# Phaser.net
KiCad netlist of a schematic drawn in Altium Designer
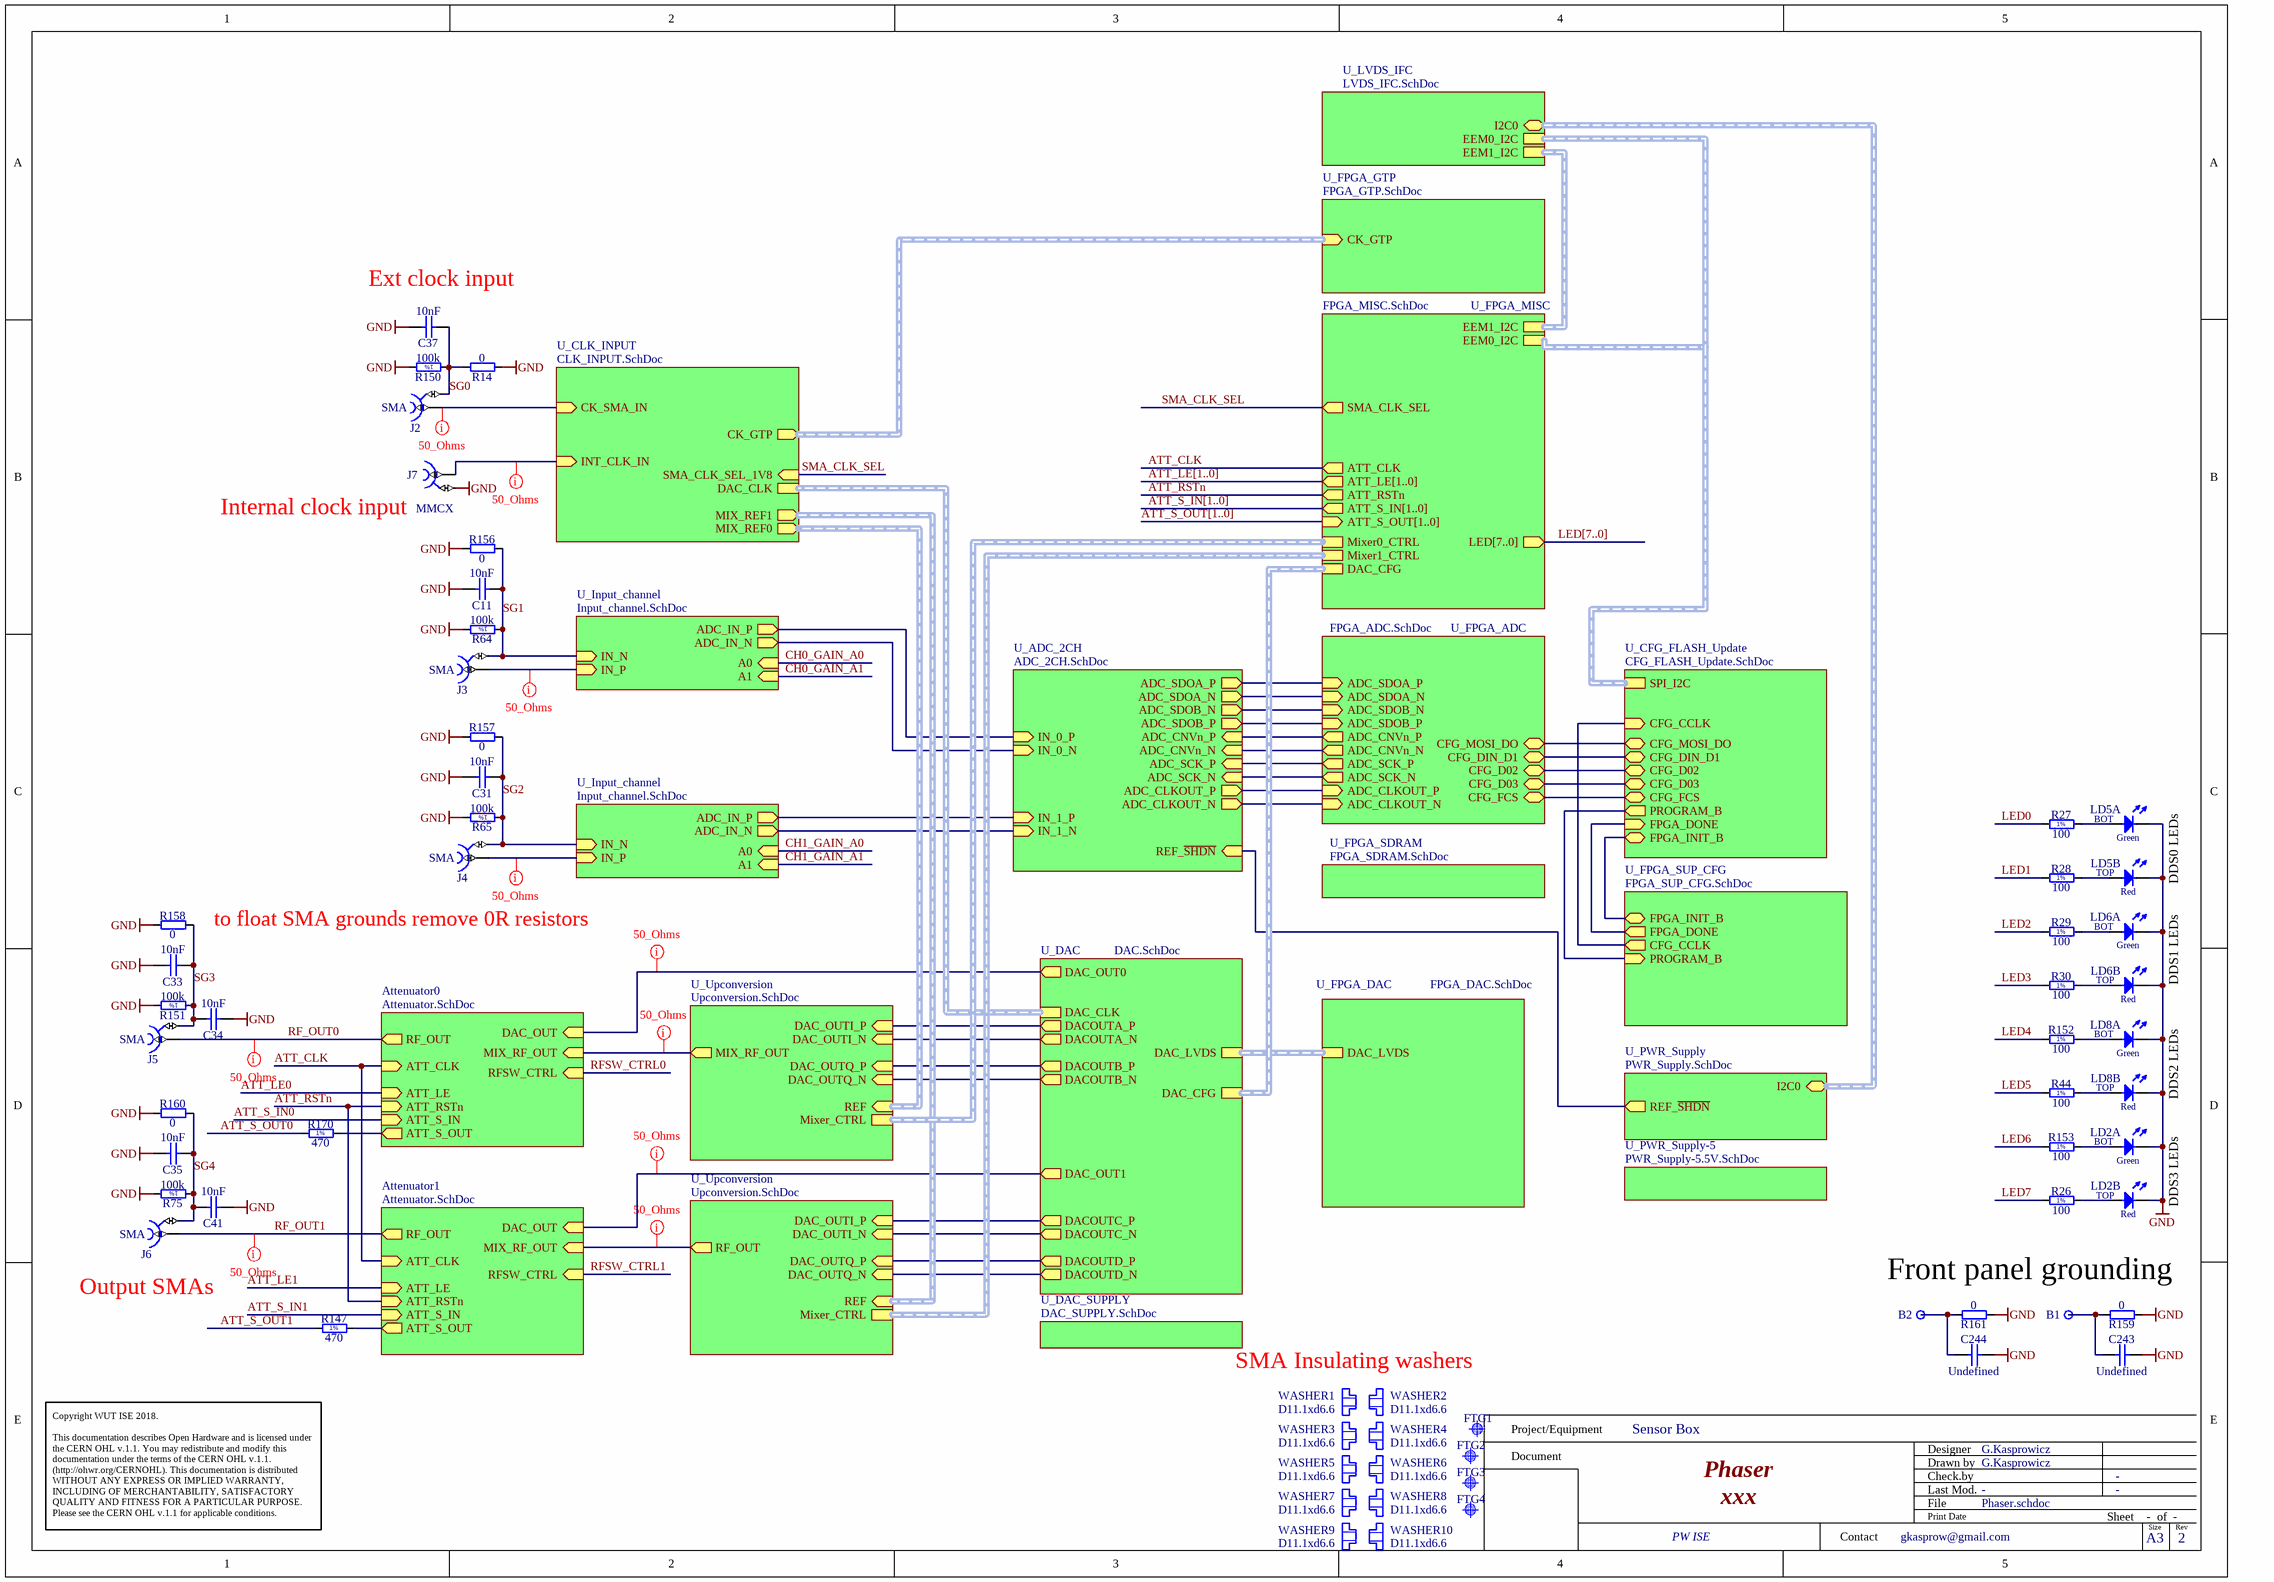
[diagram p0: Phaser.schdoc]

(export (version "E")
  (design (tool "Eeschema 10.0.6"))
  (components
    (comp (ref "B1")
      (value "Plated Hole")
      (footprint "MTG270_500")
      (description "Single Terminal Socket")
      (fields (field (name "PART NUMBER") "PLATED_HOLE2.7_PAD5.0") (field (name "AUTHOR") "CERN DEM JMW"))
      (libsource (lib "Eletro-mechanical") (part "Single Terminal Socket"))
    )
    (comp (ref "B2")
      (value "Plated Hole")
      (footprint "MTG270_500")
      (description "Single Terminal Socket")
      (fields (field (name "PART NUMBER") "PLATED_HOLE2.7_PAD5.0") (field (name "AUTHOR") "CERN DEM JMW"))
      (libsource (lib "Eletro-mechanical") (part "Single Terminal Socket"))
    )
    (comp (ref "C11")
      (value "10nF")
      (footprint "CAPC1005X55N")
      (description "Non-polarised capacitor")
      (fields
        (field (name "PART NUMBER") "CC0402_10NF_16V_10%_X7R")
        (field (name "VOLTAGE") "16V")
        (field (name "AUTHOR") "CERN DEM JLC")
      )
      (libsource (lib "Capacitors") (part "Capacitor - non polarized"))
    )
    (comp (ref "C31")
      (value "10nF")
      (footprint "CAPC1005X55N")
      (description "Non-polarised capacitor")
      (fields
        (field (name "PART NUMBER") "CC0402_10NF_16V_10%_X7R")
        (field (name "VOLTAGE") "16V")
        (field (name "AUTHOR") "CERN DEM JLC")
      )
      (libsource (lib "Capacitors") (part "Capacitor - non polarized"))
    )
    (comp (ref "C33")
      (value "10nF")
      (footprint "CAPC1005X55N")
      (description "Non-polarised capacitor")
      (fields
        (field (name "PART NUMBER") "CC0402_10NF_16V_10%_X7R")
        (field (name "VOLTAGE") "16V")
        (field (name "AUTHOR") "CERN DEM JLC")
      )
      (libsource (lib "Capacitors") (part "Capacitor - non polarized"))
    )
    (comp (ref "C34")
      (value "10nF")
      (footprint "CAPC1005X55N")
      (description "Non-polarised capacitor")
      (fields
        (field (name "PART NUMBER") "CC0402_10NF_16V_10%_X7R")
        (field (name "VOLTAGE") "16V")
        (field (name "AUTHOR") "CERN DEM JLC")
      )
      (libsource (lib "Capacitors") (part "Capacitor - non polarized"))
    )
    (comp (ref "C35")
      (value "10nF")
      (footprint "CAPC1005X55N")
      (description "Non-polarised capacitor")
      (fields
        (field (name "PART NUMBER") "CC0402_10NF_16V_10%_X7R")
        (field (name "VOLTAGE") "16V")
        (field (name "AUTHOR") "CERN DEM JLC")
      )
      (libsource (lib "Capacitors") (part "Capacitor - non polarized"))
    )
    (comp (ref "C37")
      (value "10nF")
      (footprint "CAPC1005X55N")
      (description "Non-polarised capacitor")
      (fields
        (field (name "PART NUMBER") "CC0402_10NF_16V_10%_X7R")
        (field (name "VOLTAGE") "16V")
        (field (name "AUTHOR") "CERN DEM JLC")
      )
      (libsource (lib "Capacitors") (part "Capacitor - non polarized"))
    )
    (comp (ref "C41")
      (value "10nF")
      (footprint "CAPC1005X55N")
      (description "Non-polarised capacitor")
      (fields
        (field (name "PART NUMBER") "CC0402_10NF_16V_10%_X7R")
        (field (name "VOLTAGE") "16V")
        (field (name "AUTHOR") "CERN DEM JLC")
      )
      (libsource (lib "Capacitors") (part "Capacitor - non polarized"))
    )
    (comp (ref "C243")
      (value "Undefined")
      (footprint "CAPC2012X135N")
      (description "Non-polarised capacitor")
      (fields (field (name "PART NUMBER") "CC0805_NO-VALUE") (field (name "AUTHOR") "CERN DEM JLC"))
      (libsource (lib "Capacitors") (part "Capacitor - non polarized"))
    )
    (comp (ref "C244")
      (value "Undefined")
      (footprint "CAPC2012X135N")
      (description "Non-polarised capacitor")
      (fields (field (name "PART NUMBER") "CC0805_NO-VALUE") (field (name "AUTHOR") "CERN DEM JLC"))
      (libsource (lib "Capacitors") (part "Capacitor - non polarized"))
    )
    (comp (ref "FTG1")
      (value "Use only in PCB")
      (footprint "FIDUCIAL_TOP_C100-200")
      (description "Fiducial Target")
      (fields (field (name "PART NUMBER") "FIDUCIAL_TARGET_C100-200") (field (name "AUTHOR") "CERN DEM JLC"))
      (libsource (lib "Eletro-mechanical") (part "Fiducial Target"))
    )
    (comp (ref "FTG2")
      (value "Use only in PCB")
      (footprint "FIDUCIAL_TOP_S100-200")
      (description "Fiducial Target")
      (fields (field (name "PART NUMBER") "FIDUCIAL_TARGET_S100-200") (field (name "AUTHOR") "CERN DEM JLC"))
      (libsource (lib "Eletro-mechanical") (part "Fiducial Target"))
    )
    (comp (ref "FTG3")
      (value "Use only in PCB")
      (footprint "FIDUCIAL_TOP_S200-400")
      (description "Fiducial Target")
      (fields (field (name "PART NUMBER") "FIDUCIAL_TARGET_S200-400") (field (name "AUTHOR") "CERN DEM JLC"))
      (libsource (lib "Eletro-mechanical") (part "Fiducial Target"))
    )
    (comp (ref "FTG4")
      (value "Use only in PCB")
      (footprint "FIDUCIAL_TOP_S100-200")
      (description "Fiducial Target")
      (fields (field (name "PART NUMBER") "FIDUCIAL_TARGET_S100-200") (field (name "AUTHOR") "CERN DEM JLC"))
      (libsource (lib "Eletro-mechanical") (part "Fiducial Target"))
    )
    (comp (ref "J2")
      (value "SMA")
      (footprint "RF249BT0050GHDW")
      (description "50 Ohm Through Hole SMA Right Angle PCB Jack")
      (fields
        (field (name "PART NUMBER") "AdamTech_RF249BT0050GHDW")
        (field (name "MANUFACTURER") "AdamTech")
        (field (name "AUTHOR") "GK")
      )
      (libsource (lib "LIBRARY_SCH") (part "CON_SMA_RF249BT0050GHDW"))
    )
    (comp (ref "J3")
      (value "SMA")
      (footprint "RF249BT0050GHDW")
      (description "50 Ohm Through Hole SMA Right Angle PCB Jack")
      (fields
        (field (name "PART NUMBER") "AdamTech_RF249BT0050GHDW")
        (field (name "MANUFACTURER") "AdamTech")
        (field (name "AUTHOR") "GK")
      )
      (libsource (lib "LIBRARY_SCH") (part "CON_SMA_RF249BT0050GHDW"))
    )
    (comp (ref "J4")
      (value "SMA")
      (footprint "RF249BT0050GHDW")
      (description "50 Ohm Through Hole SMA Right Angle PCB Jack")
      (fields
        (field (name "PART NUMBER") "AdamTech_RF249BT0050GHDW")
        (field (name "MANUFACTURER") "AdamTech")
        (field (name "AUTHOR") "GK")
      )
      (libsource (lib "LIBRARY_SCH") (part "CON_SMA_RF249BT0050GHDW"))
    )
    (comp (ref "J5")
      (value "SMA")
      (footprint "RF249BT0050GHDW")
      (description "50 Ohm Through Hole SMA Right Angle PCB Jack")
      (fields
        (field (name "PART NUMBER") "AdamTech_RF249BT0050GHDW")
        (field (name "MANUFACTURER") "AdamTech")
        (field (name "AUTHOR") "GK")
      )
      (libsource (lib "LIBRARY_SCH") (part "CON_SMA_RF249BT0050GHDW"))
    )
    (comp (ref "J6")
      (value "SMA")
      (footprint "RF249BT0050GHDW")
      (description "50 Ohm Through Hole SMA Right Angle PCB Jack")
      (fields
        (field (name "PART NUMBER") "AdamTech_RF249BT0050GHDW")
        (field (name "MANUFACTURER") "AdamTech")
        (field (name "AUTHOR") "GK")
      )
      (libsource (lib "LIBRARY_SCH") (part "CON_SMA_RF249BT0050GHDW"))
    )
    (comp (ref "J7")
      (value "MMCX")
      (footprint "SAMTEC_MMCX-J-P-H-ST-TH1")
      (fields
        (field (name "PART NUMBER") "SAMTEC_MMCX-J-P-H-ST-TH1")
        (field (name "MANUFACTURER") "SAMTEC")
        (field (name "MANUFACTURER PART NUMBER") "MMCX-J-P-H-ST-TH1")
        (field (name "AUTHOR") "CERN DEM JLC")
      )
      (libsource (lib "Connectors") (part "Coax_1Female_1Shield"))
    )
    (comp (ref "LD2")
      (value "Red/Green")
      (footprint "LED_DIALIGHT_571-0112F")
      (description "2x LED  Botom Green, Top Red")
      (fields
        (field (name "PART NUMBER") "LED_DIALIGHT_571-0112F")
        (field (name "MANUFACTURER") "DIALIGHT")
        (field (name "AUTHOR") "CERN DEM JLC")
      )
      (libsource (lib "ICs And Semiconductors") (part "LED x2 G-1C2A-BOT_R-3C4A-TOP"))
    )
    (comp (ref "LD5")
      (value "Red/Green")
      (footprint "LED_DIALIGHT_571-0112F")
      (description "2x LED  Botom Green, Top Red")
      (fields
        (field (name "PART NUMBER") "LED_DIALIGHT_571-0112F")
        (field (name "MANUFACTURER") "DIALIGHT")
        (field (name "AUTHOR") "CERN DEM JLC")
      )
      (libsource (lib "ICs And Semiconductors") (part "LED x2 G-1C2A-BOT_R-3C4A-TOP"))
    )
    (comp (ref "LD6")
      (value "Red/Green")
      (footprint "LED_DIALIGHT_571-0112F")
      (description "2x LED  Botom Green, Top Red")
      (fields
        (field (name "PART NUMBER") "LED_DIALIGHT_571-0112F")
        (field (name "MANUFACTURER") "DIALIGHT")
        (field (name "AUTHOR") "CERN DEM JLC")
      )
      (libsource (lib "ICs And Semiconductors") (part "LED x2 G-1C2A-BOT_R-3C4A-TOP"))
    )
    (comp (ref "LD8")
      (value "Red/Green")
      (footprint "LED_DIALIGHT_571-0112F")
      (description "2x LED  Botom Green, Top Red")
      (fields
        (field (name "PART NUMBER") "LED_DIALIGHT_571-0112F")
        (field (name "MANUFACTURER") "DIALIGHT")
        (field (name "AUTHOR") "CERN DEM JLC")
      )
      (libsource (lib "ICs And Semiconductors") (part "LED x2 G-1C2A-BOT_R-3C4A-TOP"))
    )
    (comp (ref "R14")
      (value "0")
      (footprint "RESC1608X55N")
      (description "Resistor")
      (fields
        (field (name "PART NUMBER") "R0603_0R_JUMPER")
        (field (name "MANUFACTURER") "GENERIC")
        (field (name "AUTHOR") "CERN DEM JLC")
      )
      (libsource (lib "Resistors") (part "Resistor"))
    )
    (comp (ref "R26")
      (value "100")
      (footprint "RESC1005X40N")
      (description "Resistor - 1%")
      (fields
        (field (name "PART NUMBER") "R0402_100R_1%_0.0625W_100PPM")
        (field (name "POWER") "0.0625W")
        (field (name "AUTHOR") "CERN DEM JLC")
      )
      (libsource (lib "Resistors") (part "Resistor - 1%"))
    )
    (comp (ref "R27")
      (value "100")
      (footprint "RESC1005X40N")
      (description "Resistor - 1%")
      (fields
        (field (name "PART NUMBER") "R0402_100R_1%_0.0625W_100PPM")
        (field (name "POWER") "0.0625W")
        (field (name "AUTHOR") "CERN DEM JLC")
      )
      (libsource (lib "Resistors") (part "Resistor - 1%"))
    )
    (comp (ref "R28")
      (value "100")
      (footprint "RESC1005X40N")
      (description "Resistor - 1%")
      (fields
        (field (name "PART NUMBER") "R0402_100R_1%_0.0625W_100PPM")
        (field (name "POWER") "0.0625W")
        (field (name "AUTHOR") "CERN DEM JLC")
      )
      (libsource (lib "Resistors") (part "Resistor - 1%"))
    )
    (comp (ref "R29")
      (value "100")
      (footprint "RESC1005X40N")
      (description "Resistor - 1%")
      (fields
        (field (name "PART NUMBER") "R0402_100R_1%_0.0625W_100PPM")
        (field (name "POWER") "0.0625W")
        (field (name "AUTHOR") "CERN DEM JLC")
      )
      (libsource (lib "Resistors") (part "Resistor - 1%"))
    )
    (comp (ref "R30")
      (value "100")
      (footprint "RESC1005X40N")
      (description "Resistor - 1%")
      (fields
        (field (name "PART NUMBER") "R0402_100R_1%_0.0625W_100PPM")
        (field (name "POWER") "0.0625W")
        (field (name "AUTHOR") "CERN DEM JLC")
      )
      (libsource (lib "Resistors") (part "Resistor - 1%"))
    )
    (comp (ref "R44")
      (value "100")
      (footprint "RESC1005X40N")
      (description "Resistor - 1%")
      (fields
        (field (name "PART NUMBER") "R0402_100R_1%_0.0625W_100PPM")
        (field (name "POWER") "0.0625W")
        (field (name "AUTHOR") "CERN DEM JLC")
      )
      (libsource (lib "Resistors") (part "Resistor - 1%"))
    )
    (comp (ref "R64")
      (value "100k")
      (footprint "RESC1005X40N")
      (description "Resistor - 1%")
      (fields
        (field (name "PART NUMBER") "R0402_100K_1%_0.0625W_100PPM")
        (field (name "MANUFACTURER") "GENERIC")
        (field (name "AUTHOR") "CERN DEM JLC")
      )
      (libsource (lib "Resistors") (part "Resistor - 1%"))
    )
    (comp (ref "R65")
      (value "100k")
      (footprint "RESC1005X40N")
      (description "Resistor - 1%")
      (fields
        (field (name "PART NUMBER") "R0402_100K_1%_0.0625W_100PPM")
        (field (name "MANUFACTURER") "GENERIC")
        (field (name "AUTHOR") "CERN DEM JLC")
      )
      (libsource (lib "Resistors") (part "Resistor - 1%"))
    )
    (comp (ref "R75")
      (value "100k")
      (footprint "RESC1005X40N")
      (description "Resistor - 1%")
      (fields
        (field (name "PART NUMBER") "R0402_100K_1%_0.0625W_100PPM")
        (field (name "MANUFACTURER") "GENERIC")
        (field (name "AUTHOR") "CERN DEM JLC")
      )
      (libsource (lib "Resistors") (part "Resistor - 1%"))
    )
    (comp (ref "R147")
      (value "470")
      (footprint "RESC1005X40N")
      (description "Resistor - 1%")
      (fields
        (field (name "PART NUMBER") "R0402_470R_1%_0.0625W_100PPM")
        (field (name "POWER") "0.0625W")
        (field (name "AUTHOR") "CERN DEM JLC")
      )
      (libsource (lib "Resistors") (part "Resistor - 1%"))
    )
    (comp (ref "R150")
      (value "100k")
      (footprint "RESC1005X40N")
      (description "Resistor - 1%")
      (fields
        (field (name "PART NUMBER") "R0402_100K_1%_0.0625W_100PPM")
        (field (name "MANUFACTURER") "GENERIC")
        (field (name "AUTHOR") "CERN DEM JLC")
      )
      (libsource (lib "Resistors") (part "Resistor - 1%"))
    )
    (comp (ref "R151")
      (value "100k")
      (footprint "RESC1005X40N")
      (description "Resistor - 1%")
      (fields
        (field (name "PART NUMBER") "R0402_100K_1%_0.0625W_100PPM")
        (field (name "MANUFACTURER") "GENERIC")
        (field (name "AUTHOR") "CERN DEM JLC")
      )
      (libsource (lib "Resistors") (part "Resistor - 1%"))
    )
    (comp (ref "R152")
      (value "100")
      (footprint "RESC1005X40N")
      (description "Resistor - 1%")
      (fields
        (field (name "PART NUMBER") "R0402_100R_1%_0.0625W_100PPM")
        (field (name "POWER") "0.0625W")
        (field (name "AUTHOR") "CERN DEM JLC")
      )
      (libsource (lib "Resistors") (part "Resistor - 1%"))
    )
    (comp (ref "R153")
      (value "100")
      (footprint "RESC1005X40N")
      (description "Resistor - 1%")
      (fields
        (field (name "PART NUMBER") "R0402_100R_1%_0.0625W_100PPM")
        (field (name "POWER") "0.0625W")
        (field (name "AUTHOR") "CERN DEM JLC")
      )
      (libsource (lib "Resistors") (part "Resistor - 1%"))
    )
    (comp (ref "R156")
      (value "0")
      (footprint "RESC1608X55N")
      (description "Resistor")
      (fields
        (field (name "PART NUMBER") "R0603_0R_JUMPER")
        (field (name "MANUFACTURER") "GENERIC")
        (field (name "AUTHOR") "CERN DEM JLC")
      )
      (libsource (lib "Resistors") (part "Resistor"))
    )
    (comp (ref "R157")
      (value "0")
      (footprint "RESC1608X55N")
      (description "Resistor")
      (fields
        (field (name "PART NUMBER") "R0603_0R_JUMPER")
        (field (name "MANUFACTURER") "GENERIC")
        (field (name "AUTHOR") "CERN DEM JLC")
      )
      (libsource (lib "Resistors") (part "Resistor"))
    )
    (comp (ref "R158")
      (value "0")
      (footprint "RESC1608X55N")
      (description "Resistor")
      (fields
        (field (name "PART NUMBER") "R0603_0R_JUMPER")
        (field (name "MANUFACTURER") "GENERIC")
        (field (name "AUTHOR") "CERN DEM JLC")
      )
      (libsource (lib "Resistors") (part "Resistor"))
    )
    (comp (ref "R159")
      (value "0")
      (footprint "RESC1608X55N")
      (description "Resistor")
      (fields
        (field (name "PART NUMBER") "R0603_0R_JUMPER")
        (field (name "MANUFACTURER") "GENERIC")
        (field (name "AUTHOR") "CERN DEM JLC")
      )
      (libsource (lib "Resistors") (part "Resistor"))
    )
    (comp (ref "R160")
      (value "0")
      (footprint "RESC1608X55N")
      (description "Resistor")
      (fields
        (field (name "PART NUMBER") "R0603_0R_JUMPER")
        (field (name "MANUFACTURER") "GENERIC")
        (field (name "AUTHOR") "CERN DEM JLC")
      )
      (libsource (lib "Resistors") (part "Resistor"))
    )
    (comp (ref "R161")
      (value "0")
      (footprint "RESC1608X55N")
      (description "Resistor")
      (fields
        (field (name "PART NUMBER") "R0603_0R_JUMPER")
        (field (name "MANUFACTURER") "GENERIC")
        (field (name "AUTHOR") "CERN DEM JLC")
      )
      (libsource (lib "Resistors") (part "Resistor"))
    )
    (comp (ref "R170")
      (value "470")
      (footprint "RESC1005X40N")
      (description "Resistor - 1%")
      (fields
        (field (name "PART NUMBER") "R0402_470R_1%_0.0625W_100PPM")
        (field (name "POWER") "0.0625W")
        (field (name "AUTHOR") "CERN DEM JLC")
      )
      (libsource (lib "Resistors") (part "Resistor - 1%"))
    )
    (comp (ref "WASHER1")
      (value "D11.1xd6.6")
      (footprint "Keystone_7687")
      (description "SMA_Shoulder Washer")
      (fields
        (field (name "PART NUMBER") "Keystone 7687")
        (field (name "MANUFACTURER") "Keystone")
        (field (name "AUTHOR") "GK")
      )
      (libsource (lib "LIBRARY_SCH") (part "Keystone_7687"))
    )
    (comp (ref "WASHER2")
      (value "D11.1xd6.6")
      (footprint "Keystone_7687")
      (description "SMA_Shoulder Washer")
      (fields
        (field (name "PART NUMBER") "Keystone 7687")
        (field (name "MANUFACTURER") "Keystone")
        (field (name "AUTHOR") "GK")
      )
      (libsource (lib "LIBRARY_SCH") (part "Keystone_7687"))
    )
    (comp (ref "WASHER3")
      (value "D11.1xd6.6")
      (footprint "Keystone_7687")
      (description "SMA_Shoulder Washer")
      (fields
        (field (name "PART NUMBER") "Keystone 7687")
        (field (name "MANUFACTURER") "Keystone")
        (field (name "AUTHOR") "GK")
      )
      (libsource (lib "LIBRARY_SCH") (part "Keystone_7687"))
    )
    (comp (ref "WASHER4")
      (value "D11.1xd6.6")
      (footprint "Keystone_7687")
      (description "SMA_Shoulder Washer")
      (fields
        (field (name "PART NUMBER") "Keystone 7687")
        (field (name "MANUFACTURER") "Keystone")
        (field (name "AUTHOR") "GK")
      )
      (libsource (lib "LIBRARY_SCH") (part "Keystone_7687"))
    )
    (comp (ref "WASHER5")
      (value "D11.1xd6.6")
      (footprint "Keystone_7687")
      (description "SMA_Shoulder Washer")
      (fields
        (field (name "PART NUMBER") "Keystone 7687")
        (field (name "MANUFACTURER") "Keystone")
        (field (name "AUTHOR") "GK")
      )
      (libsource (lib "LIBRARY_SCH") (part "Keystone_7687"))
    )
    (comp (ref "WASHER6")
      (value "D11.1xd6.6")
      (footprint "Keystone_7687")
      (description "SMA_Shoulder Washer")
      (fields
        (field (name "PART NUMBER") "Keystone 7687")
        (field (name "MANUFACTURER") "Keystone")
        (field (name "AUTHOR") "GK")
      )
      (libsource (lib "LIBRARY_SCH") (part "Keystone_7687"))
    )
    (comp (ref "WASHER7")
      (value "D11.1xd6.6")
      (footprint "Keystone_7687")
      (description "SMA_Shoulder Washer")
      (fields
        (field (name "PART NUMBER") "Keystone 7687")
        (field (name "MANUFACTURER") "Keystone")
        (field (name "AUTHOR") "GK")
      )
      (libsource (lib "LIBRARY_SCH") (part "Keystone_7687"))
    )
    (comp (ref "WASHER8")
      (value "D11.1xd6.6")
      (footprint "Keystone_7687")
      (description "SMA_Shoulder Washer")
      (fields
        (field (name "PART NUMBER") "Keystone 7687")
        (field (name "MANUFACTURER") "Keystone")
        (field (name "AUTHOR") "GK")
      )
      (libsource (lib "LIBRARY_SCH") (part "Keystone_7687"))
    )
    (comp (ref "WASHER9")
      (value "D11.1xd6.6")
      (footprint "Keystone_7687")
      (description "SMA_Shoulder Washer")
      (fields
        (field (name "PART NUMBER") "Keystone 7687")
        (field (name "MANUFACTURER") "Keystone")
        (field (name "AUTHOR") "GK")
      )
      (libsource (lib "LIBRARY_SCH") (part "Keystone_7687"))
    )
    (comp (ref "WASHER10")
      (value "D11.1xd6.6")
      (footprint "Keystone_7687")
      (description "SMA_Shoulder Washer")
      (fields
        (field (name "PART NUMBER") "Keystone 7687")
        (field (name "MANUFACTURER") "Keystone")
        (field (name "AUTHOR") "GK")
      )
      (libsource (lib "LIBRARY_SCH") (part "Keystone_7687"))
    )
  )
  (nets
    (net (code "23") (name "/ATT_S_OUT") (class "Default")
      (node (ref "R170") (pin "2") (pinfunction "2_2") (pintype "passive"))
    )
    (net (code "24") (name "/ATT_S_OUT0") (class "Default")
      (node (ref "R170") (pin "1") (pinfunction "1_1") (pintype "passive"))
    )
    (net (code "25") (name "/ATT_S_OUT1") (class "Default")
      (node (ref "R147") (pin "1") (pinfunction "1_1") (pintype "passive"))
    )
    (net (code "27") (name "/ATT_S_OUT_1") (class "Default")
      (node (ref "R147") (pin "2") (pinfunction "2_2") (pintype "passive"))
    )
    (net (code "39") (name "/CK_SMA_IN") (class "Default")
      (node (ref "J2") (pin "1") (pinfunction "1_1") (pintype "bidirectional"))
    )
    (net (code "58") (name "/INT_CLK_IN") (class "Default")
      (node (ref "J7") (pin "1") (pinfunction "1_1") (pintype "bidirectional"))
    )
    (net (code "59") (name "/IN_P") (class "Default")
      (node (ref "J4") (pin "1") (pinfunction "1_1") (pintype "bidirectional"))
    )
    (net (code "60") (name "/IN_P_1") (class "Default")
      (node (ref "J3") (pin "1") (pinfunction "1_1") (pintype "bidirectional"))
    )
    (net (code "61") (name "/LED0") (class "Default")
      (node (ref "R27") (pin "1") (pinfunction "1_1") (pintype "passive"))
    )
    (net (code "62") (name "/LED1") (class "Default")
      (node (ref "R28") (pin "1") (pinfunction "1_1") (pintype "passive"))
    )
    (net (code "63") (name "/LED2") (class "Default")
      (node (ref "R29") (pin "1") (pinfunction "1_1") (pintype "passive"))
    )
    (net (code "64") (name "/LED3") (class "Default")
      (node (ref "R30") (pin "1") (pinfunction "1_1") (pintype "passive"))
    )
    (net (code "65") (name "/LED4") (class "Default")
      (node (ref "R152") (pin "1") (pinfunction "1_1") (pintype "passive"))
    )
    (net (code "66") (name "/LED5") (class "Default")
      (node (ref "R44") (pin "1") (pinfunction "1_1") (pintype "passive"))
    )
    (net (code "67") (name "/LED6") (class "Default")
      (node (ref "R153") (pin "1") (pinfunction "1_1") (pintype "passive"))
    )
    (net (code "68") (name "/LED7") (class "Default")
      (node (ref "R26") (pin "1") (pinfunction "1_1") (pintype "passive"))
    )
    (net (code "80") (name "/RF_OUT0") (class "Default")
      (node (ref "J5") (pin "1") (pinfunction "1_1") (pintype "bidirectional"))
    )
    (net (code "81") (name "/RF_OUT1") (class "Default")
      (node (ref "J6") (pin "1") (pinfunction "1_1") (pintype "bidirectional"))
    )
    (net (code "82") (name "/SG0") (class "Default")
      (node (ref "C37") (pin "1") (pinfunction "1_1") (pintype "passive"))
      (node (ref "J2") (pin "2") (pinfunction "2_2") (pintype "bidirectional"))
      (node (ref "R14") (pin "2") (pinfunction "2_2") (pintype "passive"))
      (node (ref "R150") (pin "2") (pinfunction "2_2") (pintype "passive"))
    )
    (net (code "83") (name "/SG1") (class "Default")
      (node (ref "C11") (pin "1") (pinfunction "1_1") (pintype "passive"))
      (node (ref "J3") (pin "2") (pinfunction "2_2") (pintype "bidirectional"))
      (node (ref "R156") (pin "2") (pinfunction "2_2") (pintype "passive"))
      (node (ref "R64") (pin "2") (pinfunction "2_2") (pintype "passive"))
    )
    (net (code "84") (name "/SG2") (class "Default")
      (node (ref "C31") (pin "1") (pinfunction "1_1") (pintype "passive"))
      (node (ref "J4") (pin "2") (pinfunction "2_2") (pintype "bidirectional"))
      (node (ref "R157") (pin "2") (pinfunction "2_2") (pintype "passive"))
      (node (ref "R65") (pin "2") (pinfunction "2_2") (pintype "passive"))
    )
    (net (code "85") (name "/SG3") (class "Default")
      (node (ref "C33") (pin "1") (pinfunction "1_1") (pintype "passive"))
      (node (ref "C34") (pin "2") (pinfunction "2_2") (pintype "passive"))
      (node (ref "J5") (pin "2") (pinfunction "2_2") (pintype "bidirectional"))
      (node (ref "R151") (pin "2") (pinfunction "2_2") (pintype "passive"))
      (node (ref "R158") (pin "2") (pinfunction "2_2") (pintype "passive"))
    )
    (net (code "86") (name "/SG4") (class "Default")
      (node (ref "C35") (pin "1") (pinfunction "1_1") (pintype "passive"))
      (node (ref "C41") (pin "2") (pinfunction "2_2") (pintype "passive"))
      (node (ref "J6") (pin "2") (pinfunction "2_2") (pintype "bidirectional"))
      (node (ref "R160") (pin "2") (pinfunction "2_2") (pintype "passive"))
      (node (ref "R75") (pin "2") (pinfunction "2_2") (pintype "passive"))
    )
    (net (code "89") (name "GND") (class "Default")
      (node (ref "C11") (pin "2") (pinfunction "2_2") (pintype "passive"))
      (node (ref "C243") (pin "2") (pinfunction "2_2") (pintype "passive"))
      (node (ref "C244") (pin "2") (pinfunction "2_2") (pintype "passive"))
      (node (ref "C31") (pin "2") (pinfunction "2_2") (pintype "passive"))
      (node (ref "C33") (pin "2") (pinfunction "2_2") (pintype "passive"))
      (node (ref "C34") (pin "1") (pinfunction "1_1") (pintype "passive"))
      (node (ref "C35") (pin "2") (pinfunction "2_2") (pintype "passive"))
      (node (ref "C37") (pin "2") (pinfunction "2_2") (pintype "passive"))
      (node (ref "C41") (pin "1") (pinfunction "1_1") (pintype "passive"))
      (node (ref "J7") (pin "2") (pinfunction "2_2") (pintype "bidirectional"))
      (node (ref "LD2") (pin "1") (pinfunction "C_1") (pintype "passive"))
      (node (ref "LD2") (pin "3") (pinfunction "C_3") (pintype "passive"))
      (node (ref "LD5") (pin "1") (pinfunction "C_1") (pintype "passive"))
      (node (ref "LD5") (pin "3") (pinfunction "C_3") (pintype "passive"))
      (node (ref "LD6") (pin "1") (pinfunction "C_1") (pintype "passive"))
      (node (ref "LD6") (pin "3") (pinfunction "C_3") (pintype "passive"))
      (node (ref "LD8") (pin "1") (pinfunction "C_1") (pintype "passive"))
      (node (ref "LD8") (pin "3") (pinfunction "C_3") (pintype "passive"))
      (node (ref "R14") (pin "1") (pinfunction "1_1") (pintype "passive"))
      (node (ref "R150") (pin "1") (pinfunction "1_1") (pintype "passive"))
      (node (ref "R151") (pin "1") (pinfunction "1_1") (pintype "passive"))
      (node (ref "R156") (pin "1") (pinfunction "1_1") (pintype "passive"))
      (node (ref "R157") (pin "1") (pinfunction "1_1") (pintype "passive"))
      (node (ref "R158") (pin "1") (pinfunction "1_1") (pintype "passive"))
      (node (ref "R159") (pin "1") (pinfunction "1_1") (pintype "passive"))
      (node (ref "R160") (pin "1") (pinfunction "1_1") (pintype "passive"))
      (node (ref "R161") (pin "1") (pinfunction "1_1") (pintype "passive"))
      (node (ref "R64") (pin "1") (pinfunction "1_1") (pintype "passive"))
      (node (ref "R65") (pin "1") (pinfunction "1_1") (pintype "passive"))
      (node (ref "R75") (pin "1") (pinfunction "1_1") (pintype "passive"))
    )
    (net (code "90") (name "Net-(B1-Pad1)") (class "Default")
      (node (ref "B1") (pin "1") (pinfunction "1_1") (pintype "bidirectional"))
      (node (ref "C243") (pin "1") (pinfunction "1_1") (pintype "passive"))
      (node (ref "R159") (pin "2") (pinfunction "2_2") (pintype "passive"))
    )
    (net (code "91") (name "Net-(B2-Pad1)") (class "Default")
      (node (ref "B2") (pin "1") (pinfunction "1_1") (pintype "bidirectional"))
      (node (ref "C244") (pin "1") (pinfunction "1_1") (pintype "passive"))
      (node (ref "R161") (pin "2") (pinfunction "2_2") (pintype "passive"))
    )
    (net (code "92") (name "Net-(LD2A-A)") (class "Default")
      (node (ref "LD2") (pin "2") (pinfunction "A_2") (pintype "passive"))
      (node (ref "R153") (pin "2") (pinfunction "2_2") (pintype "passive"))
    )
    (net (code "93") (name "Net-(LD2B-A)") (class "Default")
      (node (ref "LD2") (pin "4") (pinfunction "A_4") (pintype "passive"))
      (node (ref "R26") (pin "2") (pinfunction "2_2") (pintype "passive"))
    )
    (net (code "94") (name "Net-(LD5A-A)") (class "Default")
      (node (ref "LD5") (pin "2") (pinfunction "A_2") (pintype "passive"))
      (node (ref "R27") (pin "2") (pinfunction "2_2") (pintype "passive"))
    )
    (net (code "95") (name "Net-(LD5B-A)") (class "Default")
      (node (ref "LD5") (pin "4") (pinfunction "A_4") (pintype "passive"))
      (node (ref "R28") (pin "2") (pinfunction "2_2") (pintype "passive"))
    )
    (net (code "96") (name "Net-(LD6A-A)") (class "Default")
      (node (ref "LD6") (pin "2") (pinfunction "A_2") (pintype "passive"))
      (node (ref "R29") (pin "2") (pinfunction "2_2") (pintype "passive"))
    )
    (net (code "97") (name "Net-(LD6B-A)") (class "Default")
      (node (ref "LD6") (pin "4") (pinfunction "A_4") (pintype "passive"))
      (node (ref "R30") (pin "2") (pinfunction "2_2") (pintype "passive"))
    )
    (net (code "98") (name "Net-(LD8A-A)") (class "Default")
      (node (ref "LD8") (pin "2") (pinfunction "A_2") (pintype "passive"))
      (node (ref "R152") (pin "2") (pinfunction "2_2") (pintype "passive"))
    )
    (net (code "99") (name "Net-(LD8B-A)") (class "Default")
      (node (ref "LD8") (pin "4") (pinfunction "A_4") (pintype "passive"))
      (node (ref "R44") (pin "2") (pinfunction "2_2") (pintype "passive"))
    )
  )
)
